# BoosterHC_HAT_V0_1.net
KiCad netlist of a schematic drawn in EAGLE
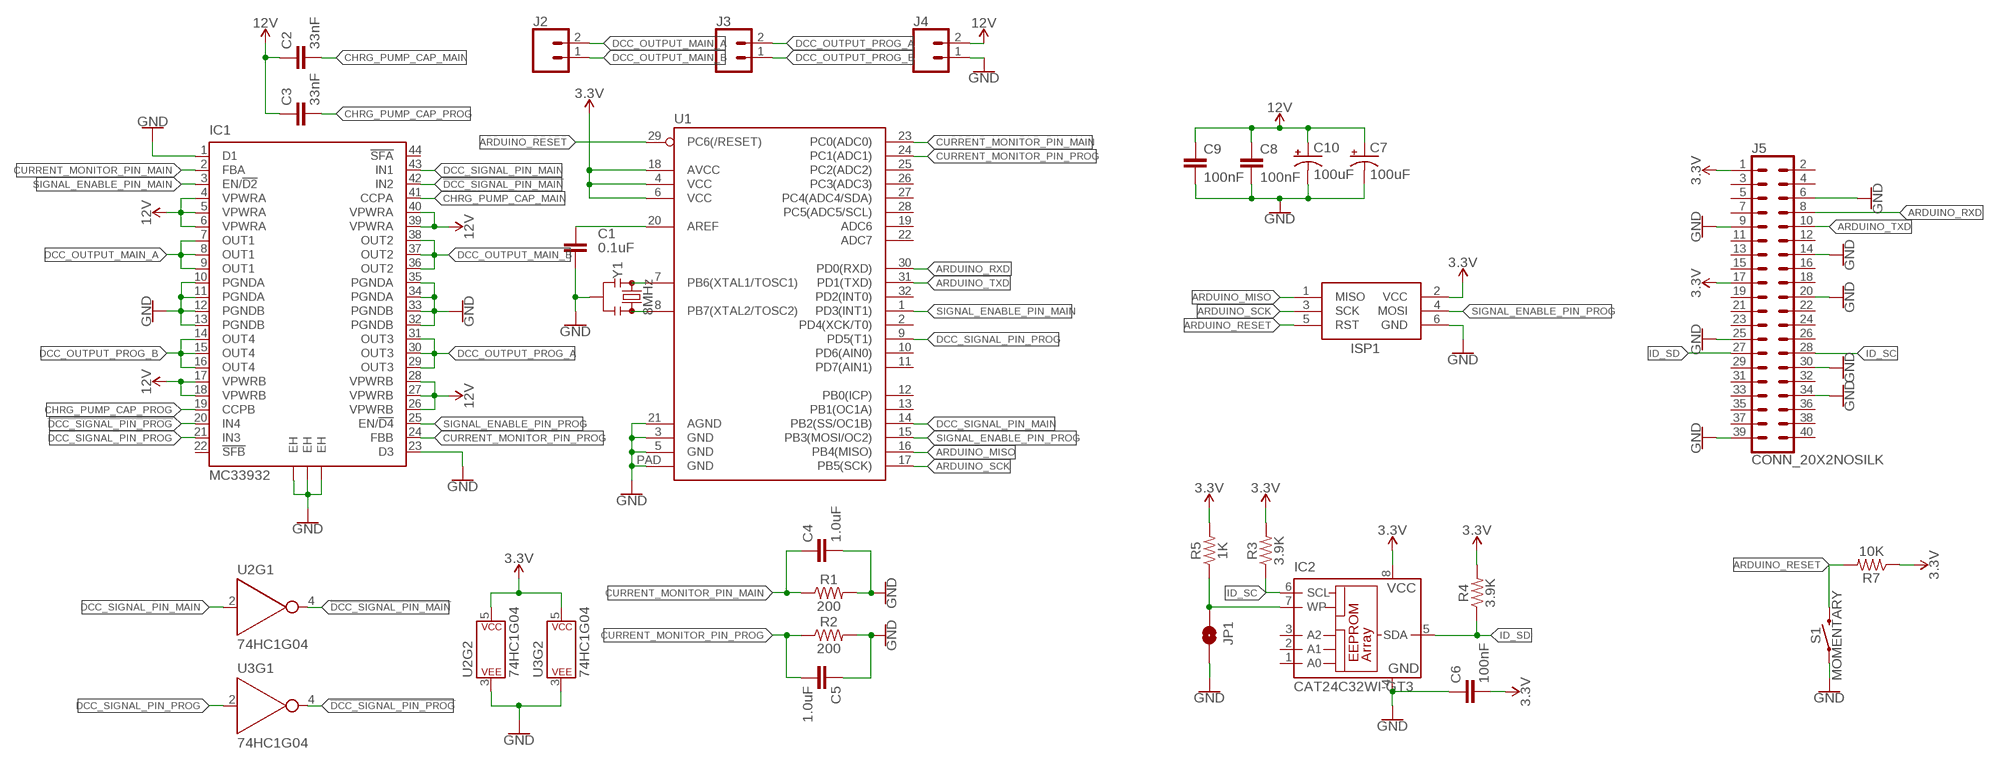
[diagram p0: schematic, sheet 1]

(export (version "E")
  (design (tool "Eeschema 10.0.6"))
  (components
    (comp (ref "C1")
      (value "0.1uF")
      (footprint "eagle-import:0603")
      (libsource (lib "eagle-import") (part "0.1UF-0603-25V-5%"))
    )
    (comp (ref "C2")
      (value "33nF")
      (footprint "eagle-import:0603")
      (libsource (lib "eagle-import") (part "33NF-0603-50V-10%"))
    )
    (comp (ref "C3")
      (value "33nF")
      (footprint "eagle-import:0603")
      (libsource (lib "eagle-import") (part "33NF-0603-50V-10%"))
    )
    (comp (ref "C4")
      (value "1.0uF")
      (footprint "eagle-import:0603")
      (libsource (lib "eagle-import") (part "1.0UF-0603-16V-10%"))
    )
    (comp (ref "C5")
      (value "1.0uF")
      (footprint "eagle-import:0603")
      (libsource (lib "eagle-import") (part "1.0UF-0603-16V-10%"))
    )
    (comp (ref "C6")
      (value "100nF")
      (footprint "eagle-import:0603")
      (libsource (lib "eagle-import") (part "33NF-0603-50V-10%"))
    )
    (comp (ref "C7")
      (value "100uF")
      (footprint "eagle-import:PANASONIC_D")
      (libsource (lib "eagle-import") (part "100UF-POLAR-25V-20%(ELEC)"))
    )
    (comp (ref "C8")
      (value "100nF")
      (footprint "eagle-import:0603")
      (libsource (lib "eagle-import") (part "47NF-0603-25V-5%"))
    )
    (comp (ref "C9")
      (value "100nF")
      (footprint "eagle-import:0603")
      (libsource (lib "eagle-import") (part "47NF-0603-25V-5%"))
    )
    (comp (ref "C10")
      (value "100uF")
      (footprint "eagle-import:PANASONIC_D")
      (libsource (lib "eagle-import") (part "100UF-POLAR-25V-20%(ELEC)"))
    )
    (comp (ref "IC1")
      (value "MC33932")
      (footprint "eagle-import:HSOP44")
      (fields (field (name "MPN") "MC33932VW"))
      (libsource (lib "eagle-import") (part "MC33932"))
    )
    (comp (ref "IC2")
      (value "CAT24C32WI-GT3")
      (footprint "eagle-import:SO-08")
      (fields (field (name "MPN") "IS24C32A-2GLI"))
      (libsource (lib "eagle-import") (part "24SNC32A"))
    )
    (comp (ref "ISP1")
      (value "AVRISP-6")
      (footprint "eagle-import:AVRISP")
      (libsource (lib "eagle-import") (part "AVRISP-6"))
    )
    (comp (ref "J2")
      (value "CONN_025MM")
      (footprint "eagle-import:SCREWTERMINAL-5MM-2")
      (libsource (lib "eagle-import") (part "CONN_025MM"))
    )
    (comp (ref "J3")
      (value "CONN_025MM")
      (footprint "eagle-import:SCREWTERMINAL-5MM-2")
      (libsource (lib "eagle-import") (part "CONN_025MM"))
    )
    (comp (ref "J4")
      (value "CONN_025MM")
      (footprint "eagle-import:SCREWTERMINAL-5MM-2")
      (libsource (lib "eagle-import") (part "CONN_025MM"))
    )
    (comp (ref "J5")
      (value "CONN_20X2NOSILK")
      (footprint "eagle-import:2X20_NOSILK")
      (libsource (lib "eagle-import") (part "CONN_20X2NOSILK"))
    )
    (comp (ref "JP1")
      (value "JUMPER-SMT_2_NO_SILK")
      (footprint "eagle-import:SMT-JUMPER_2_NO_SILK")
      (libsource (lib "eagle-import") (part "JUMPER-SMT_2_NO_SILK"))
    )
    (comp (ref "R1")
      (value "200")
      (footprint "eagle-import:0603")
      (libsource (lib "eagle-import") (part "200OHM-0603-1/10W-1%"))
    )
    (comp (ref "R2")
      (value "200")
      (footprint "eagle-import:0603")
      (libsource (lib "eagle-import") (part "200OHM-0603-1/10W-1%"))
    )
    (comp (ref "R3")
      (value "3.9K")
      (footprint "eagle-import:0603")
      (libsource (lib "eagle-import") (part "200OHM-0603-1/10W-1%"))
    )
    (comp (ref "R4")
      (value "3.9K")
      (footprint "eagle-import:0603")
      (libsource (lib "eagle-import") (part "200OHM-0603-1/10W-1%"))
    )
    (comp (ref "R5")
      (value "1K")
      (footprint "eagle-import:0603")
      (libsource (lib "eagle-import") (part "200OHM-0603-1/10W-1%"))
    )
    (comp (ref "R7")
      (value "10K")
      (footprint "eagle-import:0603")
      (libsource (lib "eagle-import") (part "200OHM-0603-1/10W-1%"))
    )
    (comp (ref "S1")
      (value "MOMENTARY")
      (footprint "eagle-import:TACTILE_SWITCH_SMD_5.2MM")
      (libsource (lib "eagle-import") (part "MOMENTARY-SWITCH-SPST-SMD-5.2-REDUNDANT"))
    )
    (comp (ref "U1")
      (value "ATMEGA328P_MLFMLF32")
      (footprint "eagle-import:MLF32-PAD")
      (libsource (lib "eagle-import") (part "ATMEGA328P_MLFMLF32"))
    )
    (comp (ref "U2")
      (value "74HC1G04")
      (footprint "eagle-import:SOT353")
      (libsource (lib "eagle-import") (part "741G04HC"))
    )
    (comp (ref "U3")
      (value "74HC1G04")
      (footprint "eagle-import:SOT353")
      (libsource (lib "eagle-import") (part "741G04HC"))
    )
    (comp (ref "Y1")
      (value "8MHz")
      (footprint "eagle-import:RESONATOR-SMD-3.2X1.3")
      (libsource (lib "eagle-import") (part "RESONATOR-8MHZSMD_3.2X1.3"))
    )
  )
  (nets
    (net (code "1") (name "/~{DCC_SIGNAL_PIN_MAIN}") (class "Default")
      (node (ref "IC1") (pin "42") (pinfunction "IN2_42") (pintype "input"))
      (node (ref "U2") (pin "4") (pinfunction "Y_4") (pintype "bidirectional"))
    )
    (net (code "2") (name "/~{DCC_SIGNAL_PIN_PROG}") (class "Default")
      (node (ref "IC1") (pin "20") (pinfunction "IN4_20") (pintype "input"))
      (node (ref "U3") (pin "4") (pinfunction "Y_4") (pintype "bidirectional"))
    )
    (net (code "3") (name "3.3V") (class "Default")
      (node (ref "C6") (pin "2") (pinfunction "2_2") (pintype "passive"))
      (node (ref "IC2") (pin "8") (pinfunction "VCC_8") (pintype "power_in"))
      (node (ref "ISP1") (pin "2") (pinfunction "VCC_2") (pintype "power_in"))
      (node (ref "J5") (pin "1") (pinfunction "1_1") (pintype "passive"))
      (node (ref "J5") (pin "17") (pinfunction "17_17") (pintype "passive"))
      (node (ref "R3") (pin "2") (pinfunction "2_2") (pintype "passive"))
      (node (ref "R4") (pin "2") (pinfunction "2_2") (pintype "passive"))
      (node (ref "R5") (pin "2") (pinfunction "2_2") (pintype "passive"))
      (node (ref "R7") (pin "1") (pinfunction "1_1") (pintype "passive"))
      (node (ref "U1") (pin "18") (pinfunction "AVCC_18") (pintype "bidirectional"))
      (node (ref "U1") (pin "4") (pinfunction "VCC_4") (pintype "bidirectional"))
      (node (ref "U1") (pin "6") (pinfunction "VCC_6") (pintype "bidirectional"))
      (node (ref "U2") (pin "5") (pinfunction "P$V+_5") (pintype "bidirectional"))
      (node (ref "U3") (pin "5") (pinfunction "P$V+_5") (pintype "bidirectional"))
    )
    (net (code "4") (name "12V") (class "Default")
      (node (ref "C10") (pin "+") (pinfunction "+_+") (pintype "passive"))
      (node (ref "C2") (pin "1") (pinfunction "1_1") (pintype "passive"))
      (node (ref "C3") (pin "1") (pinfunction "1_1") (pintype "passive"))
      (node (ref "C7") (pin "+") (pinfunction "+_+") (pintype "passive"))
      (node (ref "C8") (pin "1") (pinfunction "1_1") (pintype "passive"))
      (node (ref "C9") (pin "1") (pinfunction "1_1") (pintype "passive"))
      (node (ref "IC1") (pin "17") (pinfunction "VPWRB_17") (pintype "input"))
      (node (ref "IC1") (pin "18") (pinfunction "VPWRB_18") (pintype "input"))
      (node (ref "IC1") (pin "26") (pinfunction "VPWRB_26") (pintype "input"))
      (node (ref "IC1") (pin "27") (pinfunction "VPWRB_27") (pintype "input"))
      (node (ref "IC1") (pin "28") (pinfunction "VPWRB_28") (pintype "input"))
      (node (ref "IC1") (pin "39") (pinfunction "VPWRA_39") (pintype "input"))
      (node (ref "IC1") (pin "4") (pinfunction "VPWRA_4") (pintype "input"))
      (node (ref "IC1") (pin "40") (pinfunction "VPWRA_40") (pintype "input"))
      (node (ref "IC1") (pin "5") (pinfunction "VPWRA_5") (pintype "input"))
      (node (ref "IC1") (pin "6") (pinfunction "VPWRA_6") (pintype "input"))
      (node (ref "J4") (pin "2") (pinfunction "2_2") (pintype "passive"))
    )
    (net (code "5") (name "ARDUINO_MISO") (class "Default")
      (node (ref "ISP1") (pin "1") (pinfunction "MISO_1") (pintype "input"))
      (node (ref "U1") (pin "16") (pinfunction "PB4(MISO)_16") (pintype "bidirectional"))
    )
    (net (code "6") (name "ARDUINO_RESET") (class "Default")
      (node (ref "ISP1") (pin "5") (pinfunction "RST_5") (pintype "output"))
      (node (ref "R7") (pin "2") (pinfunction "2_2") (pintype "passive"))
      (node (ref "S1") (pin "3") (pinfunction "2_3") (pintype "passive"))
      (node (ref "S1") (pin "4") (pinfunction "2_4") (pintype "passive"))
      (node (ref "U1") (pin "29") (pinfunction "PC6(/RESET)_29") (pintype "bidirectional"))
    )
    (net (code "7") (name "ARDUINO_RXD") (class "Default")
      (node (ref "J5") (pin "8") (pinfunction "8_8") (pintype "passive"))
      (node (ref "U1") (pin "30") (pinfunction "PD0(RXD)_30") (pintype "bidirectional"))
    )
    (net (code "8") (name "ARDUINO_SCK") (class "Default")
      (node (ref "ISP1") (pin "3") (pinfunction "SCK_3") (pintype "output"))
      (node (ref "U1") (pin "17") (pinfunction "PB5(SCK)_17") (pintype "bidirectional"))
    )
    (net (code "9") (name "ARDUINO_TXD") (class "Default")
      (node (ref "J5") (pin "10") (pinfunction "10_10") (pintype "passive"))
      (node (ref "U1") (pin "31") (pinfunction "PD1(TXD)_31") (pintype "bidirectional"))
    )
    (net (code "10") (name "CHRG_PUMP_CAP_MAIN") (class "Default")
      (node (ref "C2") (pin "2") (pinfunction "2_2") (pintype "passive"))
      (node (ref "IC1") (pin "41") (pinfunction "CCPA_41") (pintype "output"))
    )
    (net (code "11") (name "CHRG_PUMP_CAP_PROG") (class "Default")
      (node (ref "C3") (pin "2") (pinfunction "2_2") (pintype "passive"))
      (node (ref "IC1") (pin "19") (pinfunction "CCPB_19") (pintype "output"))
    )
    (net (code "12") (name "CURRENT_MONITOR_PIN_MAIN") (class "Default")
      (node (ref "C4") (pin "1") (pinfunction "1_1") (pintype "passive"))
      (node (ref "IC1") (pin "2") (pinfunction "FBA_2") (pintype "output"))
      (node (ref "R1") (pin "1") (pinfunction "1_1") (pintype "passive"))
      (node (ref "U1") (pin "23") (pinfunction "PC0(ADC0)_23") (pintype "bidirectional"))
    )
    (net (code "13") (name "CURRENT_MONITOR_PIN_PROG") (class "Default")
      (node (ref "C5") (pin "2") (pinfunction "2_2") (pintype "passive"))
      (node (ref "IC1") (pin "24") (pinfunction "FBB_24") (pintype "output"))
      (node (ref "R2") (pin "1") (pinfunction "1_1") (pintype "passive"))
      (node (ref "U1") (pin "24") (pinfunction "PC1(ADC1)_24") (pintype "bidirectional"))
    )
    (net (code "14") (name "DCC_OUTPUT_MAIN_A") (class "Default")
      (node (ref "IC1") (pin "7") (pinfunction "OUT1_7") (pintype "output"))
      (node (ref "IC1") (pin "8") (pinfunction "OUT1_8") (pintype "passive"))
      (node (ref "IC1") (pin "9") (pinfunction "OUT1_9") (pintype "passive"))
      (node (ref "J2") (pin "2") (pinfunction "2_2") (pintype "passive"))
    )
    (net (code "15") (name "DCC_OUTPUT_MAIN_B") (class "Default")
      (node (ref "IC1") (pin "36") (pinfunction "OUT2_36") (pintype "output"))
      (node (ref "IC1") (pin "37") (pinfunction "OUT2_37") (pintype "passive"))
      (node (ref "IC1") (pin "38") (pinfunction "OUT2_38") (pintype "passive"))
      (node (ref "J2") (pin "1") (pinfunction "1_1") (pintype "passive"))
    )
    (net (code "16") (name "DCC_OUTPUT_PROG_A") (class "Default")
      (node (ref "IC1") (pin "29") (pinfunction "OUT3_29") (pintype "output"))
      (node (ref "IC1") (pin "30") (pinfunction "OUT3_30") (pintype "passive"))
      (node (ref "IC1") (pin "31") (pinfunction "OUT3_31") (pintype "passive"))
      (node (ref "J3") (pin "2") (pinfunction "2_2") (pintype "passive"))
    )
    (net (code "17") (name "DCC_OUTPUT_PROG_B") (class "Default")
      (node (ref "IC1") (pin "14") (pinfunction "OUT4_14") (pintype "output"))
      (node (ref "IC1") (pin "15") (pinfunction "OUT4_15") (pintype "passive"))
      (node (ref "IC1") (pin "16") (pinfunction "OUT4_16") (pintype "passive"))
      (node (ref "J3") (pin "1") (pinfunction "1_1") (pintype "passive"))
    )
    (net (code "18") (name "DCC_SIGNAL_PIN_MAIN") (class "Default")
      (node (ref "IC1") (pin "43") (pinfunction "IN1_43") (pintype "input"))
      (node (ref "U1") (pin "14") (pinfunction "PB2(SS/OC1B)_14") (pintype "bidirectional"))
      (node (ref "U2") (pin "2") (pinfunction "A_2") (pintype "bidirectional"))
    )
    (net (code "19") (name "DCC_SIGNAL_PIN_PROG") (class "Default")
      (node (ref "IC1") (pin "21") (pinfunction "IN3_21") (pintype "input"))
      (node (ref "U1") (pin "9") (pinfunction "PD5(T1)_9") (pintype "bidirectional"))
      (node (ref "U3") (pin "2") (pinfunction "A_2") (pintype "bidirectional"))
    )
    (net (code "20") (name "GND") (class "Default")
      (node (ref "C1") (pin "2") (pinfunction "2_2") (pintype "passive"))
      (node (ref "C10") (pin "-") (pinfunction "-_-") (pintype "passive"))
      (node (ref "C4") (pin "2") (pinfunction "2_2") (pintype "passive"))
      (node (ref "C5") (pin "1") (pinfunction "1_1") (pintype "passive"))
      (node (ref "C6") (pin "1") (pinfunction "1_1") (pintype "passive"))
      (node (ref "C7") (pin "-") (pinfunction "-_-") (pintype "passive"))
      (node (ref "C8") (pin "2") (pinfunction "2_2") (pintype "passive"))
      (node (ref "C9") (pin "2") (pinfunction "2_2") (pintype "passive"))
      (node (ref "IC1") (pin "1") (pinfunction "D1_1") (pintype "input"))
      (node (ref "IC1") (pin "10") (pinfunction "PGNDA_10") (pintype "power_in"))
      (node (ref "IC1") (pin "11") (pinfunction "PGNDA_11") (pintype "power_in"))
      (node (ref "IC1") (pin "12") (pinfunction "PGNDB_12") (pintype "power_in"))
      (node (ref "IC1") (pin "13") (pinfunction "PGNDB_13") (pintype "power_in"))
      (node (ref "IC1") (pin "23") (pinfunction "D3_23") (pintype "input"))
      (node (ref "IC1") (pin "32") (pinfunction "PGNDB_32") (pintype "power_in"))
      (node (ref "IC1") (pin "33") (pinfunction "PGNDB_33") (pintype "power_in"))
      (node (ref "IC1") (pin "34") (pinfunction "PGNDA_34") (pintype "power_in"))
      (node (ref "IC1") (pin "35") (pinfunction "PGNDA_35") (pintype "power_in"))
      (node (ref "IC1") (pin "EH@1") (pinfunction "EH_EH@1") (pintype "passive"))
      (node (ref "IC1") (pin "EH@2") (pinfunction "EH_EH@2") (pintype "passive"))
      (node (ref "IC1") (pin "EH@3") (pinfunction "EH_EH@3") (pintype "passive"))
      (node (ref "IC2") (pin "4") (pinfunction "GND_4") (pintype "power_in"))
      (node (ref "ISP1") (pin "6") (pinfunction "GND_6") (pintype "power_in"))
      (node (ref "J4") (pin "1") (pinfunction "1_1") (pintype "passive"))
      (node (ref "J5") (pin "14") (pinfunction "14_14") (pintype "passive"))
      (node (ref "J5") (pin "20") (pinfunction "20_20") (pintype "passive"))
      (node (ref "J5") (pin "25") (pinfunction "25_25") (pintype "passive"))
      (node (ref "J5") (pin "30") (pinfunction "30_30") (pintype "passive"))
      (node (ref "J5") (pin "34") (pinfunction "34_34") (pintype "passive"))
      (node (ref "J5") (pin "39") (pinfunction "39_39") (pintype "passive"))
      (node (ref "J5") (pin "6") (pinfunction "6_6") (pintype "passive"))
      (node (ref "J5") (pin "9") (pinfunction "9_9") (pintype "passive"))
      (node (ref "JP1") (pin "2") (pinfunction "2_2") (pintype "passive"))
      (node (ref "R1") (pin "2") (pinfunction "2_2") (pintype "passive"))
      (node (ref "R2") (pin "2") (pinfunction "2_2") (pintype "passive"))
      (node (ref "S1") (pin "1") (pinfunction "1_1") (pintype "passive"))
      (node (ref "S1") (pin "2") (pinfunction "1_2") (pintype "passive"))
      (node (ref "U1") (pin "21") (pinfunction "AGND_21") (pintype "bidirectional"))
      (node (ref "U1") (pin "3") (pinfunction "GND_3") (pintype "bidirectional"))
      (node (ref "U1") (pin "5") (pinfunction "GND_5") (pintype "bidirectional"))
      (node (ref "U1") (pin "PAD") (pinfunction "GND_PAD") (pintype "bidirectional"))
      (node (ref "U2") (pin "3") (pinfunction "P$V-_3") (pintype "bidirectional"))
      (node (ref "U3") (pin "3") (pinfunction "P$V-_3") (pintype "bidirectional"))
      (node (ref "Y1") (pin "2") (pinfunction "2_2") (pintype "passive"))
    )
    (net (code "21") (name "ID_SC") (class "Default")
      (node (ref "IC2") (pin "6") (pinfunction "SCL_6") (pintype "input"))
      (node (ref "J5") (pin "28") (pinfunction "28_28") (pintype "passive"))
      (node (ref "R3") (pin "1") (pinfunction "1_1") (pintype "passive"))
    )
    (net (code "22") (name "ID_SD") (class "Default")
      (node (ref "IC2") (pin "5") (pinfunction "SDA_5") (pintype "bidirectional"))
      (node (ref "J5") (pin "27") (pinfunction "27_27") (pintype "passive"))
      (node (ref "R4") (pin "1") (pinfunction "1_1") (pintype "passive"))
    )
    (net (code "23") (name "Net-(IC2-WP)") (class "Default")
      (node (ref "IC2") (pin "7") (pinfunction "WP_7") (pintype "input"))
      (node (ref "JP1") (pin "1") (pinfunction "1_1") (pintype "passive"))
      (node (ref "R5") (pin "1") (pinfunction "1_1") (pintype "passive"))
    )
    (net (code "24") (name "Net-(U1-AREF)") (class "Default")
      (node (ref "C1") (pin "1") (pinfunction "1_1") (pintype "passive"))
      (node (ref "U1") (pin "20") (pinfunction "AREF_20") (pintype "bidirectional"))
    )
    (net (code "25") (name "Net-(U1-PB6(XTAL1{slash}TOSC1))") (class "Default")
      (node (ref "U1") (pin "7") (pinfunction "PB6(XTAL1/TOSC1)_7") (pintype "bidirectional"))
      (node (ref "Y1") (pin "1") (pinfunction "1_1") (pintype "passive"))
    )
    (net (code "26") (name "Net-(U1-PB7(XTAL2{slash}TOSC2))") (class "Default")
      (node (ref "U1") (pin "8") (pinfunction "PB7(XTAL2/TOSC2)_8") (pintype "bidirectional"))
      (node (ref "Y1") (pin "3") (pinfunction "3_3") (pintype "passive"))
    )
    (net (code "27") (name "SIGNAL_ENABLE_PIN_MAIN") (class "Default")
      (node (ref "IC1") (pin "3") (pinfunction "EN/~{D2}_3") (pintype "input"))
      (node (ref "U1") (pin "1") (pinfunction "PD3(INT1)_1") (pintype "bidirectional"))
    )
    (net (code "28") (name "SIGNAL_ENABLE_PIN_PROG") (class "Default")
      (node (ref "IC1") (pin "25") (pinfunction "EN/~{D4}_25") (pintype "input"))
      (node (ref "ISP1") (pin "4") (pinfunction "MOSI_4") (pintype "output"))
      (node (ref "U1") (pin "15") (pinfunction "PB3(MOSI/OC2)_15") (pintype "bidirectional"))
    )
    (net (code "29") (name "unconnected-(IC1-~{SFA}-Pad44)") (class "Default")
      (node (ref "IC1") (pin "44") (pinfunction "~{SFA}_44") (pintype "open_collector"))
    )
    (net (code "30") (name "unconnected-(IC1-~{SFB}-Pad22)") (class "Default")
      (node (ref "IC1") (pin "22") (pinfunction "~{SFB}_22") (pintype "open_collector"))
    )
    (net (code "31") (name "unconnected-(IC2-A0-Pad1)") (class "Default")
      (node (ref "IC2") (pin "1") (pinfunction "A0_1") (pintype "input"))
    )
    (net (code "32") (name "unconnected-(IC2-A1-Pad2)") (class "Default")
      (node (ref "IC2") (pin "2") (pinfunction "A1_2") (pintype "input"))
    )
    (net (code "33") (name "unconnected-(IC2-A2-Pad3)") (class "Default")
      (node (ref "IC2") (pin "3") (pinfunction "A2_3") (pintype "input"))
    )
    (net (code "34") (name "unconnected-(J5-Pad2)") (class "Default")
      (node (ref "J5") (pin "2") (pinfunction "2_2") (pintype "passive"))
    )
    (net (code "35") (name "unconnected-(J5-Pad3)") (class "Default")
      (node (ref "J5") (pin "3") (pinfunction "3_3") (pintype "passive"))
    )
    (net (code "36") (name "unconnected-(J5-Pad4)") (class "Default")
      (node (ref "J5") (pin "4") (pinfunction "4_4") (pintype "passive"))
    )
    (net (code "37") (name "unconnected-(J5-Pad5)") (class "Default")
      (node (ref "J5") (pin "5") (pinfunction "5_5") (pintype "passive"))
    )
    (net (code "38") (name "unconnected-(J5-Pad7)") (class "Default")
      (node (ref "J5") (pin "7") (pinfunction "7_7") (pintype "passive"))
    )
    (net (code "39") (name "unconnected-(J5-Pad11)") (class "Default")
      (node (ref "J5") (pin "11") (pinfunction "11_11") (pintype "passive"))
    )
    (net (code "40") (name "unconnected-(J5-Pad12)") (class "Default")
      (node (ref "J5") (pin "12") (pinfunction "12_12") (pintype "passive"))
    )
    (net (code "41") (name "unconnected-(J5-Pad13)") (class "Default")
      (node (ref "J5") (pin "13") (pinfunction "13_13") (pintype "passive"))
    )
    (net (code "42") (name "unconnected-(J5-Pad15)") (class "Default")
      (node (ref "J5") (pin "15") (pinfunction "15_15") (pintype "passive"))
    )
    (net (code "43") (name "unconnected-(J5-Pad16)") (class "Default")
      (node (ref "J5") (pin "16") (pinfunction "16_16") (pintype "passive"))
    )
    (net (code "44") (name "unconnected-(J5-Pad18)") (class "Default")
      (node (ref "J5") (pin "18") (pinfunction "18_18") (pintype "passive"))
    )
    (net (code "45") (name "unconnected-(J5-Pad19)") (class "Default")
      (node (ref "J5") (pin "19") (pinfunction "19_19") (pintype "passive"))
    )
    (net (code "46") (name "unconnected-(J5-Pad21)") (class "Default")
      (node (ref "J5") (pin "21") (pinfunction "21_21") (pintype "passive"))
    )
    (net (code "47") (name "unconnected-(J5-Pad22)") (class "Default")
      (node (ref "J5") (pin "22") (pinfunction "22_22") (pintype "passive"))
    )
    (net (code "48") (name "unconnected-(J5-Pad23)") (class "Default")
      (node (ref "J5") (pin "23") (pinfunction "23_23") (pintype "passive"))
    )
    (net (code "49") (name "unconnected-(J5-Pad24)") (class "Default")
      (node (ref "J5") (pin "24") (pinfunction "24_24") (pintype "passive"))
    )
    (net (code "50") (name "unconnected-(J5-Pad26)") (class "Default")
      (node (ref "J5") (pin "26") (pinfunction "26_26") (pintype "passive"))
    )
    (net (code "51") (name "unconnected-(J5-Pad29)") (class "Default")
      (node (ref "J5") (pin "29") (pinfunction "29_29") (pintype "passive"))
    )
    (net (code "52") (name "unconnected-(J5-Pad31)") (class "Default")
      (node (ref "J5") (pin "31") (pinfunction "31_31") (pintype "passive"))
    )
    (net (code "53") (name "unconnected-(J5-Pad32)") (class "Default")
      (node (ref "J5") (pin "32") (pinfunction "32_32") (pintype "passive"))
    )
    (net (code "54") (name "unconnected-(J5-Pad33)") (class "Default")
      (node (ref "J5") (pin "33") (pinfunction "33_33") (pintype "passive"))
    )
    (net (code "55") (name "unconnected-(J5-Pad35)") (class "Default")
      (node (ref "J5") (pin "35") (pinfunction "35_35") (pintype "passive"))
    )
    (net (code "56") (name "unconnected-(J5-Pad36)") (class "Default")
      (node (ref "J5") (pin "36") (pinfunction "36_36") (pintype "passive"))
    )
    (net (code "57") (name "unconnected-(J5-Pad37)") (class "Default")
      (node (ref "J5") (pin "37") (pinfunction "37_37") (pintype "passive"))
    )
    (net (code "58") (name "unconnected-(J5-Pad38)") (class "Default")
      (node (ref "J5") (pin "38") (pinfunction "38_38") (pintype "passive"))
    )
    (net (code "59") (name "unconnected-(J5-Pad40)") (class "Default")
      (node (ref "J5") (pin "40") (pinfunction "40_40") (pintype "passive"))
    )
    (net (code "60") (name "unconnected-(U1-ADC6-Pad19)") (class "Default")
      (node (ref "U1") (pin "19") (pinfunction "ADC6_19") (pintype "bidirectional"))
    )
    (net (code "61") (name "unconnected-(U1-ADC7-Pad22)") (class "Default")
      (node (ref "U1") (pin "22") (pinfunction "ADC7_22") (pintype "bidirectional"))
    )
    (net (code "62") (name "unconnected-(U1-PB0(ICP)-Pad12)") (class "Default")
      (node (ref "U1") (pin "12") (pinfunction "PB0(ICP)_12") (pintype "bidirectional"))
    )
    (net (code "63") (name "unconnected-(U1-PB1(OC1A)-Pad13)") (class "Default")
      (node (ref "U1") (pin "13") (pinfunction "PB1(OC1A)_13") (pintype "bidirectional"))
    )
    (net (code "64") (name "unconnected-(U1-PC2(ADC2)-Pad25)") (class "Default")
      (node (ref "U1") (pin "25") (pinfunction "PC2(ADC2)_25") (pintype "bidirectional"))
    )
    (net (code "65") (name "unconnected-(U1-PC3(ADC3)-Pad26)") (class "Default")
      (node (ref "U1") (pin "26") (pinfunction "PC3(ADC3)_26") (pintype "bidirectional"))
    )
    (net (code "66") (name "unconnected-(U1-PC4(ADC4{slash}SDA)-Pad27)") (class "Default")
      (node (ref "U1") (pin "27") (pinfunction "PC4(ADC4/SDA)_27") (pintype "bidirectional"))
    )
    (net (code "67") (name "unconnected-(U1-PC5(ADC5{slash}SCL)-Pad28)") (class "Default")
      (node (ref "U1") (pin "28") (pinfunction "PC5(ADC5/SCL)_28") (pintype "bidirectional"))
    )
    (net (code "68") (name "unconnected-(U1-PD2(INT0)-Pad32)") (class "Default")
      (node (ref "U1") (pin "32") (pinfunction "PD2(INT0)_32") (pintype "bidirectional"))
    )
    (net (code "69") (name "unconnected-(U1-PD4(XCK{slash}T0)-Pad2)") (class "Default")
      (node (ref "U1") (pin "2") (pinfunction "PD4(XCK/T0)_2") (pintype "bidirectional"))
    )
    (net (code "70") (name "unconnected-(U1-PD6(AIN0)-Pad10)") (class "Default")
      (node (ref "U1") (pin "10") (pinfunction "PD6(AIN0)_10") (pintype "bidirectional"))
    )
    (net (code "71") (name "unconnected-(U1-PD7(AIN1)-Pad11)") (class "Default")
      (node (ref "U1") (pin "11") (pinfunction "PD7(AIN1)_11") (pintype "bidirectional"))
    )
  )
)
